# LissajousRevB.net
KiCad netlist of a schematic drawn in EAGLE
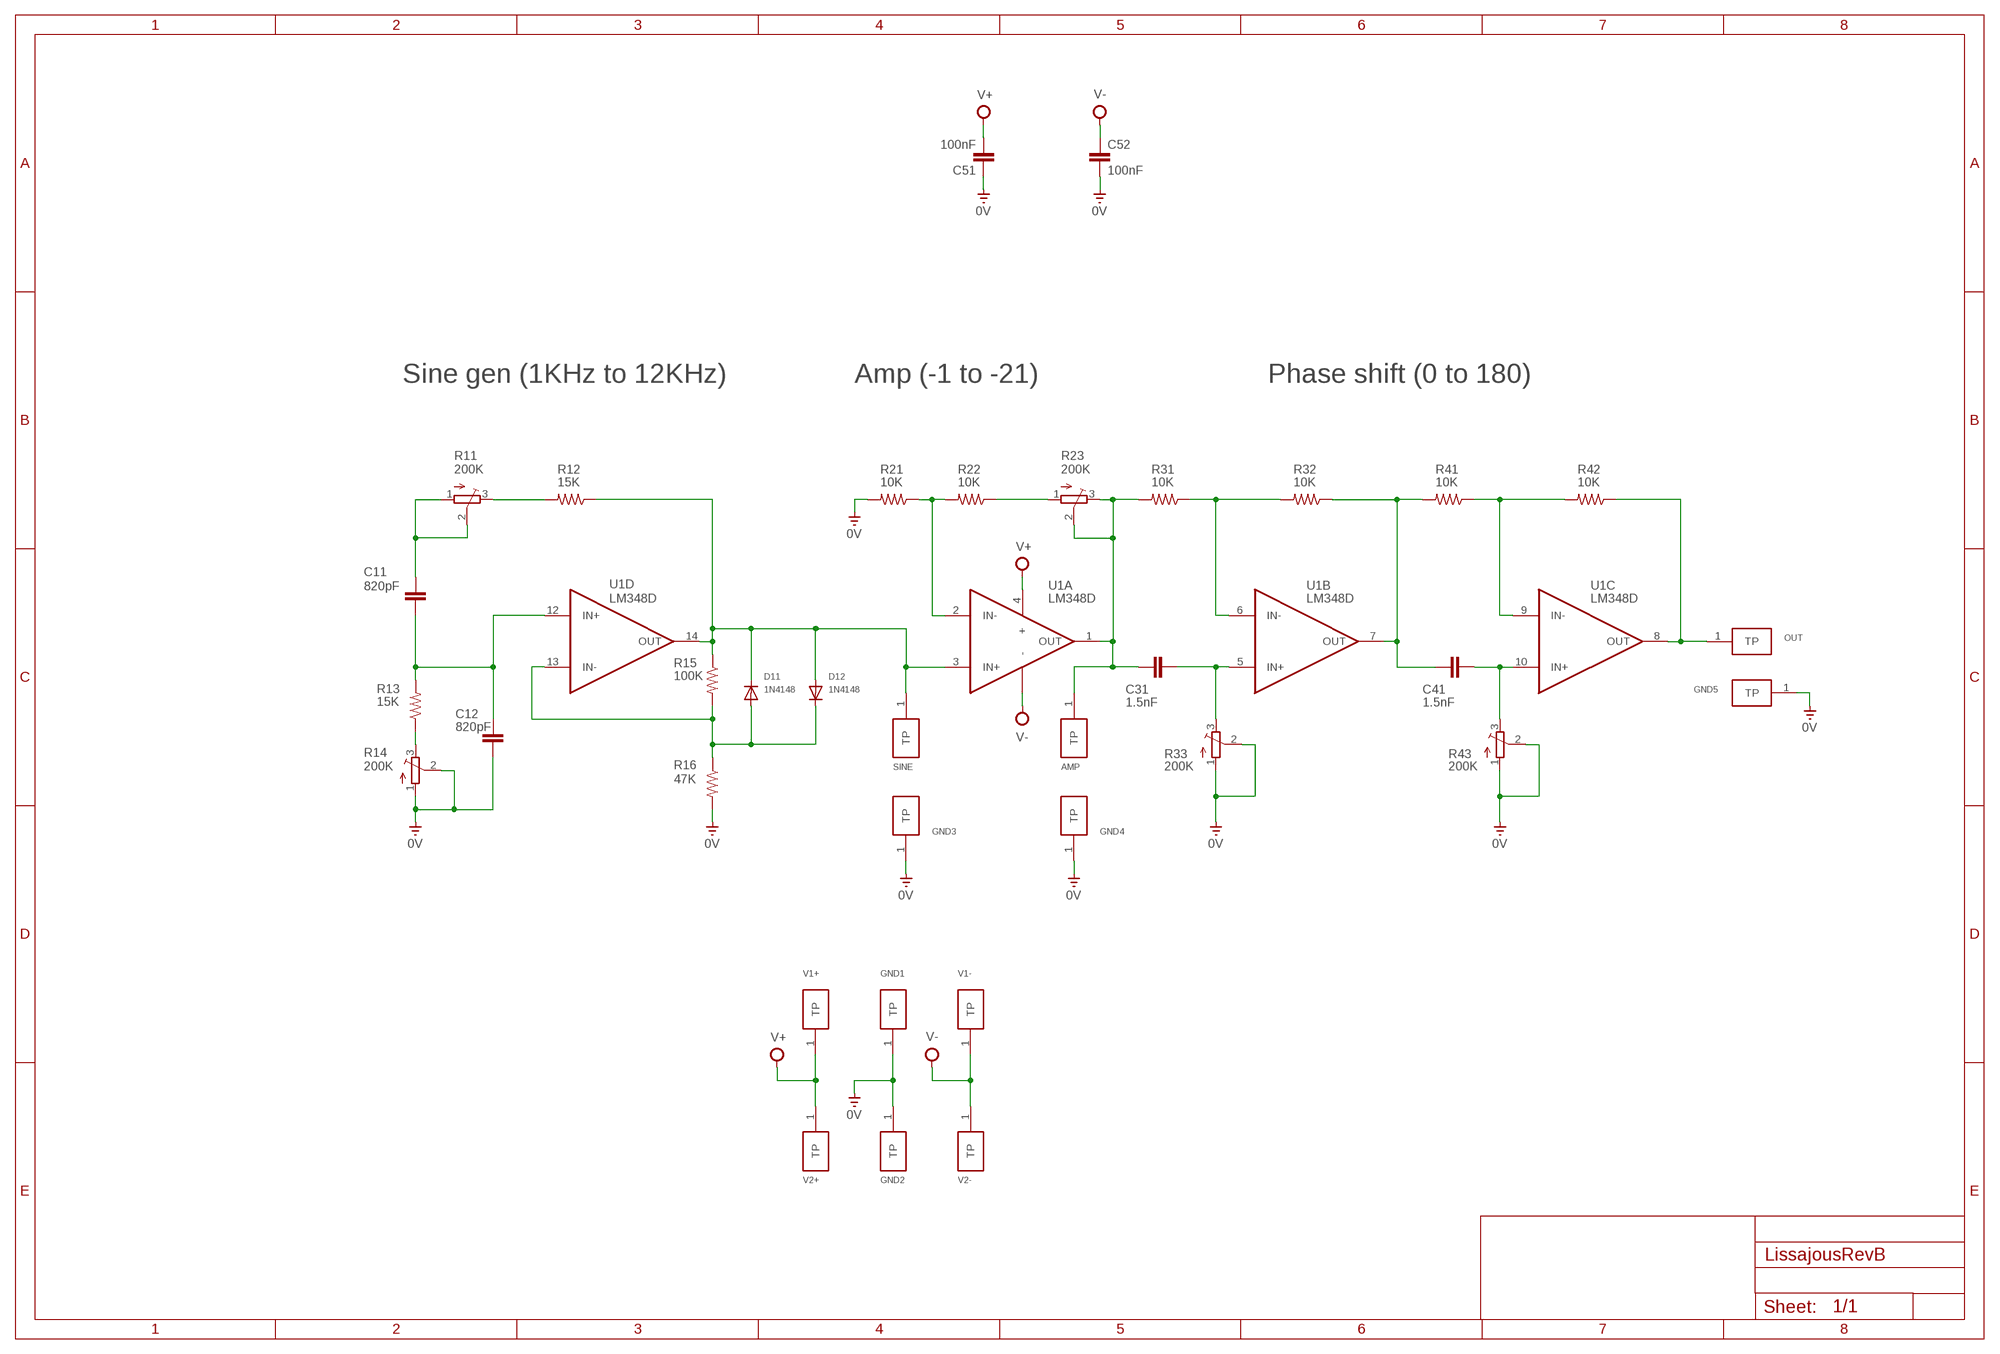
[diagram p0: schematic, sheet 1]

(export (version "E")
  (design (tool "Eeschema 10.0.6"))
  (components
    (comp (ref "AMP")
      (value "TESTPADS")
      (footprint "eagle-import:TEST")
      (libsource (lib "eagle-import") (part "TESTPADS"))
    )
    (comp (ref "C11")
      (value "820pF")
      (footprint "eagle-import:0603-CAP")
      (libsource (lib "eagle-import") (part "CAP0603-CAP"))
    )
    (comp (ref "C12")
      (value "820pF")
      (footprint "eagle-import:0603-CAP")
      (libsource (lib "eagle-import") (part "CAP0603-CAP"))
    )
    (comp (ref "C31")
      (value "1.5nF")
      (footprint "eagle-import:0603-CAP")
      (libsource (lib "eagle-import") (part "CAP0603-CAP"))
    )
    (comp (ref "C41")
      (value "1.5nF")
      (footprint "eagle-import:0603-CAP")
      (libsource (lib "eagle-import") (part "CAP0603-CAP"))
    )
    (comp (ref "C51")
      (value "100nF")
      (footprint "eagle-import:0603-CAP")
      (libsource (lib "eagle-import") (part "CAP0603-CAP"))
    )
    (comp (ref "C52")
      (value "100nF")
      (footprint "eagle-import:0603-CAP")
      (libsource (lib "eagle-import") (part "CAP0603-CAP"))
    )
    (comp (ref "D11")
      (value "1N4148")
      (footprint "eagle-import:SMADIODE")
      (libsource (lib "eagle-import") (part "DIODESMA"))
    )
    (comp (ref "D12")
      (value "1N4148")
      (footprint "eagle-import:SMADIODE")
      (libsource (lib "eagle-import") (part "DIODESMA"))
    )
    (comp (ref "GND1")
      (value "TESTPADS")
      (footprint "eagle-import:TEST")
      (libsource (lib "eagle-import") (part "TESTPADS"))
    )
    (comp (ref "GND2")
      (value "TESTPADS")
      (footprint "eagle-import:TEST")
      (libsource (lib "eagle-import") (part "TESTPADS"))
    )
    (comp (ref "GND3")
      (value "TESTPADS")
      (footprint "eagle-import:TEST")
      (libsource (lib "eagle-import") (part "TESTPADS"))
    )
    (comp (ref "GND4")
      (value "TESTPADS")
      (footprint "eagle-import:TEST")
      (libsource (lib "eagle-import") (part "TESTPADS"))
    )
    (comp (ref "GND5")
      (value "TESTPADS")
      (footprint "eagle-import:TEST")
      (libsource (lib "eagle-import") (part "TESTPADS"))
    )
    (comp (ref "OUT")
      (value "TESTPADS")
      (footprint "eagle-import:TEST")
      (libsource (lib "eagle-import") (part "TESTPADS"))
    )
    (comp (ref "R11")
      (value "200K")
      (footprint "eagle-import:TC33X")
      (libsource (lib "eagle-import") (part "TRIMPOTTC33X"))
    )
    (comp (ref "R12")
      (value "15K")
      (footprint "eagle-import:0603-RES")
      (libsource (lib "eagle-import") (part "RESISTOR0603-RES"))
    )
    (comp (ref "R13")
      (value "15K")
      (footprint "eagle-import:0603-RES")
      (libsource (lib "eagle-import") (part "RESISTOR0603-RES"))
    )
    (comp (ref "R14")
      (value "200K")
      (footprint "eagle-import:TC33X")
      (libsource (lib "eagle-import") (part "TRIMPOTTC33X"))
    )
    (comp (ref "R15")
      (value "100K")
      (footprint "eagle-import:0603-RES")
      (libsource (lib "eagle-import") (part "RESISTOR0603-RES"))
    )
    (comp (ref "R16")
      (value "47K")
      (footprint "eagle-import:0603-RES")
      (libsource (lib "eagle-import") (part "RESISTOR0603-RES"))
    )
    (comp (ref "R21")
      (value "10K")
      (footprint "eagle-import:0603-RES")
      (libsource (lib "eagle-import") (part "RESISTOR0603-RES"))
    )
    (comp (ref "R22")
      (value "10K")
      (footprint "eagle-import:0603-RES")
      (libsource (lib "eagle-import") (part "RESISTOR0603-RES"))
    )
    (comp (ref "R23")
      (value "200K")
      (footprint "eagle-import:TC33X")
      (libsource (lib "eagle-import") (part "TRIMPOTTC33X"))
    )
    (comp (ref "R31")
      (value "10K")
      (footprint "eagle-import:0603-RES")
      (libsource (lib "eagle-import") (part "RESISTOR0603-RES"))
    )
    (comp (ref "R32")
      (value "10K")
      (footprint "eagle-import:0603-RES")
      (libsource (lib "eagle-import") (part "RESISTOR0603-RES"))
    )
    (comp (ref "R33")
      (value "200K")
      (footprint "eagle-import:TC33X")
      (libsource (lib "eagle-import") (part "TRIMPOTTC33X"))
    )
    (comp (ref "R41")
      (value "10K")
      (footprint "eagle-import:0603-RES")
      (libsource (lib "eagle-import") (part "RESISTOR0603-RES"))
    )
    (comp (ref "R42")
      (value "10K")
      (footprint "eagle-import:0603-RES")
      (libsource (lib "eagle-import") (part "RESISTOR0603-RES"))
    )
    (comp (ref "R43")
      (value "200K")
      (footprint "eagle-import:TC33X")
      (libsource (lib "eagle-import") (part "TRIMPOTTC33X"))
    )
    (comp (ref "SINE")
      (value "TESTPADS")
      (footprint "eagle-import:TEST")
      (libsource (lib "eagle-import") (part "TESTPADS"))
    )
    (comp (ref "U1")
      (value "LM348D")
      (footprint "eagle-import:SOIC127P600X175-14N")
      (libsource (lib "eagle-import") (part "LM348D"))
    )
    (comp (ref "V1+")
      (value "TESTPADS")
      (footprint "eagle-import:TEST")
      (libsource (lib "eagle-import") (part "TESTPADS"))
    )
    (comp (ref "V1-")
      (value "TESTPADS")
      (footprint "eagle-import:TEST")
      (libsource (lib "eagle-import") (part "TESTPADS"))
    )
    (comp (ref "V2+")
      (value "TESTPADS")
      (footprint "eagle-import:TEST")
      (libsource (lib "eagle-import") (part "TESTPADS"))
    )
    (comp (ref "V2-")
      (value "TESTPADS")
      (footprint "eagle-import:TEST")
      (libsource (lib "eagle-import") (part "TESTPADS"))
    )
  )
  (nets
    (net (code "1") (name "0V") (class "Default")
      (node (ref "C12") (pin "1") (pinfunction "1_1") (pintype "passive"))
      (node (ref "C51") (pin "1") (pinfunction "1_1") (pintype "passive"))
      (node (ref "C52") (pin "2") (pinfunction "2_2") (pintype "passive"))
      (node (ref "GND1") (pin "1") (pinfunction "TP_1") (pintype "bidirectional"))
      (node (ref "GND2") (pin "1") (pinfunction "TP_1") (pintype "bidirectional"))
      (node (ref "GND3") (pin "1") (pinfunction "TP_1") (pintype "bidirectional"))
      (node (ref "GND4") (pin "1") (pinfunction "TP_1") (pintype "bidirectional"))
      (node (ref "GND5") (pin "1") (pinfunction "TP_1") (pintype "bidirectional"))
      (node (ref "R14") (pin "1") (pinfunction "A_1") (pintype "passive"))
      (node (ref "R14") (pin "2") (pinfunction "S_2") (pintype "passive"))
      (node (ref "R16") (pin "2") (pinfunction "2_2") (pintype "passive"))
      (node (ref "R21") (pin "2") (pinfunction "2_2") (pintype "passive"))
      (node (ref "R33") (pin "1") (pinfunction "A_1") (pintype "passive"))
      (node (ref "R33") (pin "2") (pinfunction "S_2") (pintype "passive"))
      (node (ref "R43") (pin "1") (pinfunction "A_1") (pintype "passive"))
      (node (ref "R43") (pin "2") (pinfunction "S_2") (pintype "passive"))
    )
    (net (code "2") (name "Net-(AMP-TP)") (class "Default")
      (node (ref "AMP") (pin "1") (pinfunction "TP_1") (pintype "bidirectional"))
      (node (ref "C31") (pin "2") (pinfunction "2_2") (pintype "passive"))
      (node (ref "R23") (pin "2") (pinfunction "S_2") (pintype "passive"))
      (node (ref "R23") (pin "3") (pinfunction "E_3") (pintype "passive"))
      (node (ref "R31") (pin "2") (pinfunction "2_2") (pintype "passive"))
      (node (ref "U1") (pin "1") (pinfunction "OUT_1") (pintype "output"))
    )
    (net (code "3") (name "Net-(OUT-TP)") (class "Default")
      (node (ref "OUT") (pin "1") (pinfunction "TP_1") (pintype "bidirectional"))
      (node (ref "R42") (pin "1") (pinfunction "1_1") (pintype "passive"))
      (node (ref "U1") (pin "8") (pinfunction "OUT_8") (pintype "output"))
    )
    (net (code "4") (name "Net-(R11-A)") (class "Default")
      (node (ref "C11") (pin "2") (pinfunction "2_2") (pintype "passive"))
      (node (ref "R11") (pin "1") (pinfunction "A_1") (pintype "passive"))
      (node (ref "R11") (pin "2") (pinfunction "S_2") (pintype "passive"))
    )
    (net (code "5") (name "Net-(R11-E)") (class "Default")
      (node (ref "R11") (pin "3") (pinfunction "E_3") (pintype "passive"))
      (node (ref "R12") (pin "2") (pinfunction "2_2") (pintype "passive"))
    )
    (net (code "6") (name "Net-(R14-E)") (class "Default")
      (node (ref "R13") (pin "1") (pinfunction "1_1") (pintype "passive"))
      (node (ref "R14") (pin "3") (pinfunction "E_3") (pintype "passive"))
    )
    (net (code "7") (name "Net-(R23-A)") (class "Default")
      (node (ref "R22") (pin "1") (pinfunction "1_1") (pintype "passive"))
      (node (ref "R23") (pin "1") (pinfunction "A_1") (pintype "passive"))
    )
    (net (code "8") (name "Net-(R33-E)") (class "Default")
      (node (ref "C31") (pin "1") (pinfunction "1_1") (pintype "passive"))
      (node (ref "R33") (pin "3") (pinfunction "E_3") (pintype "passive"))
      (node (ref "U1") (pin "5") (pinfunction "IN+_5") (pintype "output"))
    )
    (net (code "9") (name "Net-(R43-E)") (class "Default")
      (node (ref "C41") (pin "1") (pinfunction "1_1") (pintype "passive"))
      (node (ref "R43") (pin "3") (pinfunction "E_3") (pintype "passive"))
      (node (ref "U1") (pin "10") (pinfunction "IN+_10") (pintype "output"))
    )
    (net (code "10") (name "Net-(SINE-TP)") (class "Default")
      (node (ref "D11") (pin "C") (pinfunction "C_C") (pintype "passive"))
      (node (ref "D12") (pin "A") (pinfunction "A_A") (pintype "passive"))
      (node (ref "R12") (pin "1") (pinfunction "1_1") (pintype "passive"))
      (node (ref "R15") (pin "1") (pinfunction "1_1") (pintype "passive"))
      (node (ref "SINE") (pin "1") (pinfunction "TP_1") (pintype "bidirectional"))
      (node (ref "U1") (pin "14") (pinfunction "OUT_14") (pintype "output"))
      (node (ref "U1") (pin "3") (pinfunction "IN+_3") (pintype "output"))
    )
    (net (code "11") (name "Net-(U1A-IN-)") (class "Default")
      (node (ref "R21") (pin "1") (pinfunction "1_1") (pintype "passive"))
      (node (ref "R22") (pin "2") (pinfunction "2_2") (pintype "passive"))
      (node (ref "U1") (pin "2") (pinfunction "IN-_2") (pintype "output"))
    )
    (net (code "12") (name "Net-(U1B-IN-)") (class "Default")
      (node (ref "R31") (pin "1") (pinfunction "1_1") (pintype "passive"))
      (node (ref "R32") (pin "2") (pinfunction "2_2") (pintype "passive"))
      (node (ref "U1") (pin "6") (pinfunction "IN-_6") (pintype "output"))
    )
    (net (code "13") (name "Net-(U1B-OUT)") (class "Default")
      (node (ref "C41") (pin "2") (pinfunction "2_2") (pintype "passive"))
      (node (ref "R32") (pin "1") (pinfunction "1_1") (pintype "passive"))
      (node (ref "R41") (pin "2") (pinfunction "2_2") (pintype "passive"))
      (node (ref "U1") (pin "7") (pinfunction "OUT_7") (pintype "output"))
    )
    (net (code "14") (name "Net-(U1C-IN-)") (class "Default")
      (node (ref "R41") (pin "1") (pinfunction "1_1") (pintype "passive"))
      (node (ref "R42") (pin "2") (pinfunction "2_2") (pintype "passive"))
      (node (ref "U1") (pin "9") (pinfunction "IN-_9") (pintype "output"))
    )
    (net (code "15") (name "Net-(U1D-IN+)") (class "Default")
      (node (ref "C11") (pin "1") (pinfunction "1_1") (pintype "passive"))
      (node (ref "C12") (pin "2") (pinfunction "2_2") (pintype "passive"))
      (node (ref "R13") (pin "2") (pinfunction "2_2") (pintype "passive"))
      (node (ref "U1") (pin "12") (pinfunction "IN+_12") (pintype "output"))
    )
    (net (code "16") (name "Net-(U1D-IN-)") (class "Default")
      (node (ref "D11") (pin "A") (pinfunction "A_A") (pintype "passive"))
      (node (ref "D12") (pin "C") (pinfunction "C_C") (pintype "passive"))
      (node (ref "R15") (pin "2") (pinfunction "2_2") (pintype "passive"))
      (node (ref "R16") (pin "1") (pinfunction "1_1") (pintype "passive"))
      (node (ref "U1") (pin "13") (pinfunction "IN-_13") (pintype "output"))
    )
    (net (code "17") (name "V+") (class "Default")
      (node (ref "C51") (pin "2") (pinfunction "2_2") (pintype "passive"))
      (node (ref "U1") (pin "4") (pinfunction "+_4") (pintype "output"))
      (node (ref "V1+") (pin "1") (pinfunction "TP_1") (pintype "bidirectional"))
      (node (ref "V2+") (pin "1") (pinfunction "TP_1") (pintype "bidirectional"))
    )
    (net (code "18") (name "V-") (class "Default")
      (node (ref "C52") (pin "1") (pinfunction "1_1") (pintype "passive"))
      (node (ref "U1") (pin "11") (pinfunction "-_11") (pintype "output"))
      (node (ref "V1-") (pin "1") (pinfunction "TP_1") (pintype "bidirectional"))
      (node (ref "V2-") (pin "1") (pinfunction "TP_1") (pintype "bidirectional"))
    )
  )
)
